# FoamBot_Arduino_Pololu_servo_r2.net
KiCad netlist of a schematic drawn in EAGLE
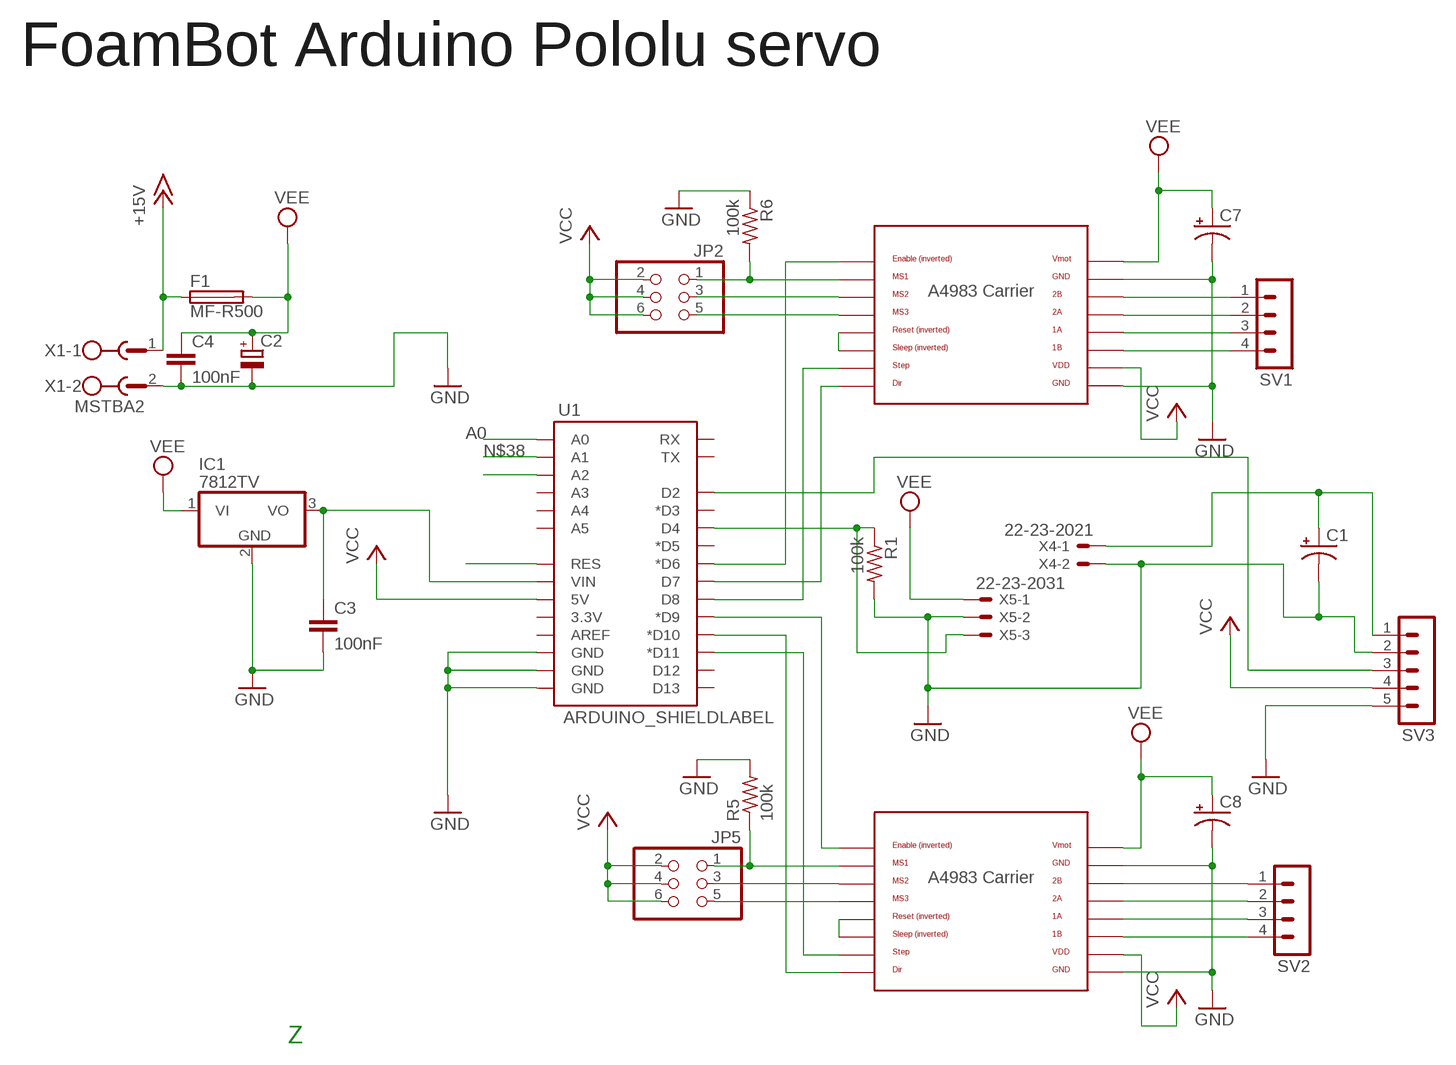
[diagram p0: schematic, sheet 1]

(export (version "E")
  (design (tool "Eeschema 10.0.6"))
  (components
    (comp (ref "C1")
      (value "CPOL-USE5-10.5")
      (footprint "eagle-import:E5-10,5")
      (libsource (lib "eagle-import") (part "CPOL-USE5-10.5"))
    )
    (comp (ref "C2")
      (value "CPOL-EUE7.5-16")
      (footprint "eagle-import:E7,5-16")
      (libsource (lib "eagle-import") (part "CPOL-EUE7.5-16"))
    )
    (comp (ref "C3")
      (value "100nF")
      (footprint "eagle-import:C2.5-3")
      (libsource (lib "eagle-import") (part "C2,5-3"))
    )
    (comp (ref "C4")
      (value "100nF")
      (footprint "eagle-import:C2.5-3")
      (libsource (lib "eagle-import") (part "C2,5-3"))
    )
    (comp (ref "C7")
      (value "CAP_POLPTH2")
      (footprint "eagle-import:CPOL-RADIAL-10UF-25V")
      (libsource (lib "eagle-import") (part "CAP_POLPTH2"))
    )
    (comp (ref "C8")
      (value "CAP_POLPTH2")
      (footprint "eagle-import:CPOL-RADIAL-10UF-25V")
      (libsource (lib "eagle-import") (part "CAP_POLPTH2"))
    )
    (comp (ref "F1")
      (value "MF-R500")
      (footprint "eagle-import:LITTLEFUSE")
      (libsource (lib "eagle-import") (part "LITTLEFUSE"))
    )
    (comp (ref "IC1")
      (value "7812TV")
      (footprint "eagle-import:TO220V")
      (libsource (lib "eagle-import") (part "78TV12"))
    )
    (comp (ref "JP2")
      (value "PINHD-2X3")
      (footprint "eagle-import:2X03")
      (libsource (lib "eagle-import") (part "PINHD-2X3"))
    )
    (comp (ref "JP5")
      (value "PINHD-2X3")
      (footprint "eagle-import:2X03")
      (libsource (lib "eagle-import") (part "PINHD-2X3"))
    )
    (comp (ref "R1")
      (value "100k")
      (footprint "eagle-import:0207_7")
      (libsource (lib "eagle-import") (part "R-US_0207/7"))
    )
    (comp (ref "R5")
      (value "100k")
      (footprint "eagle-import:0207_7")
      (libsource (lib "eagle-import") (part "R-US_0207/7"))
    )
    (comp (ref "R6")
      (value "100k")
      (footprint "eagle-import:0207_7")
      (libsource (lib "eagle-import") (part "R-US_0207/7"))
    )
    (comp (ref "SV1")
      (value "MA04-1")
      (footprint "eagle-import:MA04-1")
      (libsource (lib "eagle-import") (part "MA04-1"))
    )
    (comp (ref "SV2")
      (value "MA04-1")
      (footprint "eagle-import:MA04-1")
      (libsource (lib "eagle-import") (part "MA04-1"))
    )
    (comp (ref "SV3")
      (value "MA05-1")
      (footprint "eagle-import:MA05-1")
      (libsource (lib "eagle-import") (part "MA05-1"))
    )
    (comp (ref "U1")
      (value "ARDUINO_SHIELDLABEL")
      (footprint "eagle-import:DUEMILANOVE_SHIELD")
      (libsource (lib "eagle-import") (part "ARDUINO_SHIELDLABEL"))
    )
    (comp (ref "U2")
      (value "POLOLU_A4983CARRIER")
      (footprint "eagle-import:A4983CARRIER")
      (libsource (lib "eagle-import") (part "POLOLU_A4983CARRIER"))
    )
    (comp (ref "U3")
      (value "POLOLU_A4983CARRIER")
      (footprint "eagle-import:A4983CARRIER")
      (libsource (lib "eagle-import") (part "POLOLU_A4983CARRIER"))
    )
    (comp (ref "X1")
      (value "MSTBA2")
      (footprint "eagle-import:MSTBA2")
      (fields (field (name "MF") "FARNELL") (field (name "MPN") "1757242"))
      (libsource (lib "eagle-import") (part "MSTBA2"))
    )
    (comp (ref "X4")
      (value "22-23-2021")
      (footprint "eagle-import:22-23-2021")
      (fields (field (name "MF") "MOLEX"))
      (libsource (lib "eagle-import") (part "22-23-2021"))
    )
    (comp (ref "X5")
      (value "22-23-2031")
      (footprint "eagle-import:22-23-2031")
      (fields (field (name "MF") "MOLEX"))
      (libsource (lib "eagle-import") (part "22-23-2031"))
    )
  )
  (nets
    (net (code "1") (name "+15V") (class "Default")
      (node (ref "F1") (pin "1") (pinfunction "1_1") (pintype "passive"))
      (node (ref "X1") (pin "1") (pinfunction "1_1") (pintype "passive"))
    )
    (net (code "2") (name "/A0") (class "Default")
      (node (ref "U1") (pin "A0") (pinfunction "A0_A0") (pintype "bidirectional"))
    )
    (net (code "3") (name "/N$38") (class "Default")
      (node (ref "U1") (pin "A1") (pinfunction "A1_A1") (pintype "bidirectional"))
    )
    (net (code "4") (name "GND") (class "Default")
      (node (ref "C1") (pin "-") (pinfunction "-_-") (pintype "passive"))
      (node (ref "C2") (pin "-") (pinfunction "-_-") (pintype "passive"))
      (node (ref "C3") (pin "2") (pinfunction "2_2") (pintype "passive"))
      (node (ref "C4") (pin "2") (pinfunction "2_2") (pintype "passive"))
      (node (ref "C7") (pin "2") (pinfunction "-_2") (pintype "passive"))
      (node (ref "C8") (pin "2") (pinfunction "-_2") (pintype "passive"))
      (node (ref "IC1") (pin "2") (pinfunction "GND_2") (pintype "passive"))
      (node (ref "R1") (pin "2") (pinfunction "2_2") (pintype "passive"))
      (node (ref "R5") (pin "2") (pinfunction "2_2") (pintype "passive"))
      (node (ref "R6") (pin "1") (pinfunction "1_1") (pintype "passive"))
      (node (ref "SV3") (pin "2") (pinfunction "2_2") (pintype "passive"))
      (node (ref "SV3") (pin "5") (pinfunction "5_5") (pintype "passive"))
      (node (ref "U1") (pin "GND@0") (pinfunction "GND_GND@0") (pintype "bidirectional"))
      (node (ref "U1") (pin "GND@1") (pinfunction "GND_GND@1") (pintype "bidirectional"))
      (node (ref "U1") (pin "GND@2") (pinfunction "GND_GND@2") (pintype "bidirectional"))
      (node (ref "U2") (pin "GND") (pinfunction "GND_GND") (pintype "power_in"))
      (node (ref "U2") (pin "GND@0") (pinfunction "GND_GND@0") (pintype "power_in"))
      (node (ref "U3") (pin "GND") (pinfunction "GND_GND") (pintype "power_in"))
      (node (ref "U3") (pin "GND@0") (pinfunction "GND_GND@0") (pintype "power_in"))
      (node (ref "X1") (pin "2") (pinfunction "1_2") (pintype "passive"))
      (node (ref "X4") (pin "2") (pinfunction "S_2") (pintype "passive"))
      (node (ref "X5") (pin "2") (pinfunction "S_2") (pintype "passive"))
    )
    (net (code "5") (name "Net-(IC1-VO)") (class "Default")
      (node (ref "C3") (pin "1") (pinfunction "1_1") (pintype "passive"))
      (node (ref "IC1") (pin "3") (pinfunction "VO_3") (pintype "passive"))
      (node (ref "U1") (pin "VIN") (pinfunction "VIN_VIN") (pintype "bidirectional"))
    )
    (net (code "6") (name "Net-(JP2-Pad1)") (class "Default")
      (node (ref "JP2") (pin "1") (pinfunction "1_1") (pintype "passive"))
      (node (ref "R6") (pin "2") (pinfunction "2_2") (pintype "passive"))
      (node (ref "U2") (pin "MS1") (pinfunction "MS1_MS1") (pintype "input"))
    )
    (net (code "7") (name "Net-(JP2-Pad3)") (class "Default")
      (node (ref "JP2") (pin "3") (pinfunction "3_3") (pintype "passive"))
      (node (ref "U2") (pin "MS2") (pinfunction "MS2_MS2") (pintype "input"))
    )
    (net (code "8") (name "Net-(JP2-Pad5)") (class "Default")
      (node (ref "JP2") (pin "5") (pinfunction "5_5") (pintype "passive"))
      (node (ref "U2") (pin "MS3") (pinfunction "MS3_MS3") (pintype "input"))
    )
    (net (code "9") (name "Net-(JP5-Pad1)") (class "Default")
      (node (ref "JP5") (pin "1") (pinfunction "1_1") (pintype "passive"))
      (node (ref "R5") (pin "1") (pinfunction "1_1") (pintype "passive"))
      (node (ref "U3") (pin "MS1") (pinfunction "MS1_MS1") (pintype "input"))
    )
    (net (code "10") (name "Net-(JP5-Pad3)") (class "Default")
      (node (ref "JP5") (pin "3") (pinfunction "3_3") (pintype "passive"))
      (node (ref "U3") (pin "MS2") (pinfunction "MS2_MS2") (pintype "input"))
    )
    (net (code "11") (name "Net-(JP5-Pad5)") (class "Default")
      (node (ref "JP5") (pin "5") (pinfunction "5_5") (pintype "passive"))
      (node (ref "U3") (pin "MS3") (pinfunction "MS3_MS3") (pintype "input"))
    )
    (net (code "12") (name "Net-(SV1-Pad1)") (class "Default")
      (node (ref "SV1") (pin "1") (pinfunction "1_1") (pintype "passive"))
      (node (ref "U2") (pin "2B") (pinfunction "2B_2B") (pintype "output"))
    )
    (net (code "13") (name "Net-(SV1-Pad2)") (class "Default")
      (node (ref "SV1") (pin "2") (pinfunction "2_2") (pintype "passive"))
      (node (ref "U2") (pin "2A") (pinfunction "2A_2A") (pintype "output"))
    )
    (net (code "14") (name "Net-(SV1-Pad3)") (class "Default")
      (node (ref "SV1") (pin "3") (pinfunction "3_3") (pintype "passive"))
      (node (ref "U2") (pin "1A") (pinfunction "1A_1A") (pintype "output"))
    )
    (net (code "15") (name "Net-(SV1-Pad4)") (class "Default")
      (node (ref "SV1") (pin "4") (pinfunction "4_4") (pintype "passive"))
      (node (ref "U2") (pin "1B") (pinfunction "1B_1B") (pintype "output"))
    )
    (net (code "16") (name "Net-(SV2-Pad1)") (class "Default")
      (node (ref "SV2") (pin "1") (pinfunction "1_1") (pintype "passive"))
      (node (ref "U3") (pin "2B") (pinfunction "2B_2B") (pintype "output"))
    )
    (net (code "17") (name "Net-(SV2-Pad2)") (class "Default")
      (node (ref "SV2") (pin "2") (pinfunction "2_2") (pintype "passive"))
      (node (ref "U3") (pin "2A") (pinfunction "2A_2A") (pintype "output"))
    )
    (net (code "18") (name "Net-(SV2-Pad3)") (class "Default")
      (node (ref "SV2") (pin "3") (pinfunction "3_3") (pintype "passive"))
      (node (ref "U3") (pin "1A") (pinfunction "1A_1A") (pintype "output"))
    )
    (net (code "19") (name "Net-(SV2-Pad4)") (class "Default")
      (node (ref "SV2") (pin "4") (pinfunction "4_4") (pintype "passive"))
      (node (ref "U3") (pin "1B") (pinfunction "1B_1B") (pintype "output"))
    )
    (net (code "20") (name "Net-(SV3-Pad3)") (class "Default")
      (node (ref "SV3") (pin "3") (pinfunction "3_3") (pintype "passive"))
      (node (ref "U1") (pin "D2") (pinfunction "D2_D2") (pintype "bidirectional"))
    )
    (net (code "21") (name "Net-(U1-*D6)") (class "Default")
      (node (ref "U1") (pin "D6") (pinfunction "*D6_D6") (pintype "bidirectional"))
      (node (ref "U2") (pin "EN") (pinfunction "EN_EN") (pintype "input"))
    )
    (net (code "22") (name "Net-(U1-*D9)") (class "Default")
      (node (ref "U1") (pin "D9") (pinfunction "*D9_D9") (pintype "bidirectional"))
      (node (ref "U3") (pin "EN") (pinfunction "EN_EN") (pintype "input"))
    )
    (net (code "23") (name "Net-(U1-*D10)") (class "Default")
      (node (ref "U1") (pin "D10") (pinfunction "*D10_D10") (pintype "bidirectional"))
      (node (ref "U3") (pin "DIR") (pinfunction "DIR_DIR") (pintype "input"))
    )
    (net (code "24") (name "Net-(U1-*D11)") (class "Default")
      (node (ref "U1") (pin "D11") (pinfunction "*D11_D11") (pintype "bidirectional"))
      (node (ref "U3") (pin "STEP") (pinfunction "STEP_STEP") (pintype "input"))
    )
    (net (code "25") (name "Net-(U1-PadD7)") (class "Default")
      (node (ref "U1") (pin "D7") (pinfunction "D7_D7") (pintype "bidirectional"))
      (node (ref "U2") (pin "DIR") (pinfunction "DIR_DIR") (pintype "input"))
    )
    (net (code "26") (name "Net-(U1-PadD8)") (class "Default")
      (node (ref "U1") (pin "D8") (pinfunction "D8_D8") (pintype "bidirectional"))
      (node (ref "U2") (pin "STEP") (pinfunction "STEP_STEP") (pintype "input"))
    )
    (net (code "27") (name "Net-(U2-SLEEP)") (class "Default")
      (node (ref "U2") (pin "RST") (pinfunction "RST_RST") (pintype "input"))
      (node (ref "U2") (pin "SLP") (pinfunction "SLEEP_SLP") (pintype "input"))
    )
    (net (code "28") (name "Net-(U3-SLEEP)") (class "Default")
      (node (ref "U3") (pin "RST") (pinfunction "RST_RST") (pintype "input"))
      (node (ref "U3") (pin "SLP") (pinfunction "SLEEP_SLP") (pintype "input"))
    )
    (net (code "29") (name "Net-(X4A-S)") (class "Default")
      (node (ref "C1") (pin "+") (pinfunction "+_+") (pintype "passive"))
      (node (ref "SV3") (pin "1") (pinfunction "1_1") (pintype "passive"))
      (node (ref "X4") (pin "1") (pinfunction "S_1") (pintype "passive"))
    )
    (net (code "30") (name "Net-(X5C-S)") (class "Default")
      (node (ref "R1") (pin "1") (pinfunction "1_1") (pintype "passive"))
      (node (ref "U1") (pin "D4") (pinfunction "D4_D4") (pintype "bidirectional"))
      (node (ref "X5") (pin "3") (pinfunction "S_3") (pintype "passive"))
    )
    (net (code "31") (name "VCC") (class "Default")
      (node (ref "JP2") (pin "2") (pinfunction "2_2") (pintype "passive"))
      (node (ref "JP2") (pin "4") (pinfunction "4_4") (pintype "passive"))
      (node (ref "JP2") (pin "6") (pinfunction "6_6") (pintype "passive"))
      (node (ref "JP5") (pin "2") (pinfunction "2_2") (pintype "passive"))
      (node (ref "JP5") (pin "4") (pinfunction "4_4") (pintype "passive"))
      (node (ref "JP5") (pin "6") (pinfunction "6_6") (pintype "passive"))
      (node (ref "SV3") (pin "4") (pinfunction "4_4") (pintype "passive"))
      (node (ref "U1") (pin "5V") (pinfunction "5V_5V") (pintype "bidirectional"))
      (node (ref "U2") (pin "VDD") (pinfunction "VDD_VDD") (pintype "power_in"))
      (node (ref "U3") (pin "VDD") (pinfunction "VDD_VDD") (pintype "power_in"))
    )
    (net (code "32") (name "VEE") (class "Default")
      (node (ref "C2") (pin "+") (pinfunction "+_+") (pintype "passive"))
      (node (ref "C4") (pin "1") (pinfunction "1_1") (pintype "passive"))
      (node (ref "C7") (pin "1") (pinfunction "+_1") (pintype "passive"))
      (node (ref "C8") (pin "1") (pinfunction "+_1") (pintype "passive"))
      (node (ref "F1") (pin "2") (pinfunction "2_2") (pintype "passive"))
      (node (ref "IC1") (pin "1") (pinfunction "VI_1") (pintype "input"))
      (node (ref "U2") (pin "VMOT") (pinfunction "VMOT_VMOT") (pintype "power_in"))
      (node (ref "U3") (pin "VMOT") (pinfunction "VMOT_VMOT") (pintype "power_in"))
      (node (ref "X5") (pin "1") (pinfunction "S_1") (pintype "passive"))
    )
    (net (code "33") (name "unconnected-(U1-*D3-PadD3)") (class "Default")
      (node (ref "U1") (pin "D3") (pinfunction "*D3_D3") (pintype "bidirectional"))
    )
    (net (code "34") (name "unconnected-(U1-*D5-PadD5)") (class "Default")
      (node (ref "U1") (pin "D5") (pinfunction "*D5_D5") (pintype "bidirectional"))
    )
    (net (code "35") (name "unconnected-(U1-Pad3.3V)") (class "Default")
      (node (ref "U1") (pin "3.3V") (pinfunction "3.3V_3.3V") (pintype "bidirectional"))
    )
    (net (code "36") (name "unconnected-(U1-PadA2)") (class "Default")
      (node (ref "U1") (pin "A2") (pinfunction "A2_A2") (pintype "bidirectional"))
    )
    (net (code "37") (name "unconnected-(U1-PadA3)") (class "Default")
      (node (ref "U1") (pin "A3") (pinfunction "A3_A3") (pintype "bidirectional"))
    )
    (net (code "38") (name "unconnected-(U1-PadA4)") (class "Default")
      (node (ref "U1") (pin "A4") (pinfunction "A4_A4") (pintype "bidirectional"))
    )
    (net (code "39") (name "unconnected-(U1-PadA5)") (class "Default")
      (node (ref "U1") (pin "A5") (pinfunction "A5_A5") (pintype "bidirectional"))
    )
    (net (code "40") (name "unconnected-(U1-PadAREF)") (class "Default")
      (node (ref "U1") (pin "AREF") (pinfunction "AREF_AREF") (pintype "bidirectional"))
    )
    (net (code "41") (name "unconnected-(U1-PadD12)") (class "Default")
      (node (ref "U1") (pin "D12") (pinfunction "D12_D12") (pintype "bidirectional"))
    )
    (net (code "42") (name "unconnected-(U1-PadD13)") (class "Default")
      (node (ref "U1") (pin "D13") (pinfunction "D13_D13") (pintype "bidirectional"))
    )
    (net (code "43") (name "unconnected-(U1-PadRES)") (class "Default")
      (node (ref "U1") (pin "RES") (pinfunction "RES_RES") (pintype "bidirectional"))
    )
    (net (code "44") (name "unconnected-(U1-PadRX)") (class "Default")
      (node (ref "U1") (pin "RX") (pinfunction "RX_RX") (pintype "bidirectional"))
    )
    (net (code "45") (name "unconnected-(U1-PadTX)") (class "Default")
      (node (ref "U1") (pin "TX") (pinfunction "TX_TX") (pintype "bidirectional"))
    )
  )
)
